# CT100-channel.net
KiCad netlist of a schematic drawn in Altium Designer
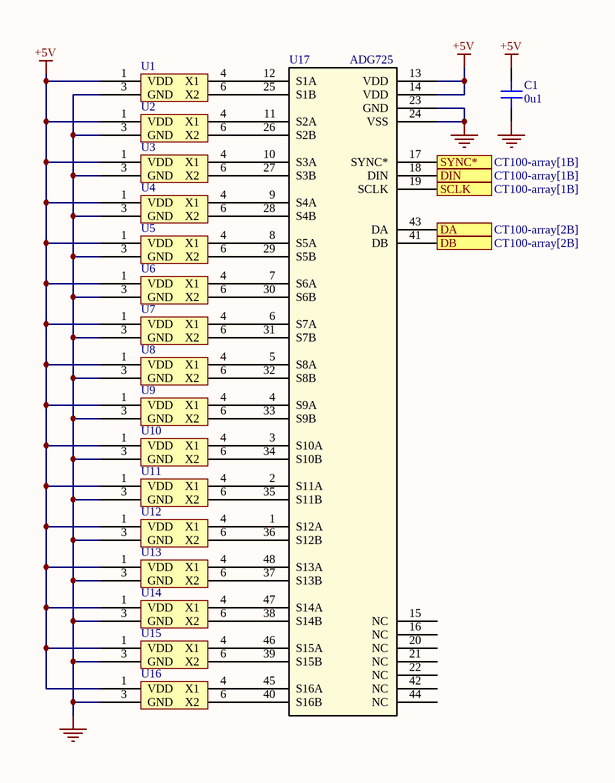
[diagram p0: CT100-channel.SchDoc]

(export (version "E")
  (design (tool "Eeschema 10.0.6"))
  (components
    (comp (ref "C1")
      (value "0u1")
      (footprint "CAP_0402")
      (description "Capacitor SMD 0402")
      (fields (field (name "VOLTAGE") "50V"))
      (libsource (lib "symbols") (part "CAP_0402"))
    )
    (comp (ref "U1")
      (value "CT100")
      (footprint "SON_6_CT100")
      (description "TMR Sensor, Linear, -40 to 85deg C")
      (fields
        (field (name "MANUFACTURER") "Crocus Technology")
        (field (name "MANUFACTURER PART NUMBER") "CT100LW-ID6")
      )
      (libsource (lib "symbols") (part "CT100LW-ID6-M"))
    )
    (comp (ref "U2")
      (value "CT100")
      (footprint "SON_6_CT100")
      (description "TMR Sensor, Linear, -40 to 85deg C")
      (fields
        (field (name "MANUFACTURER") "Crocus Technology")
        (field (name "MANUFACTURER PART NUMBER") "CT100LW-ID6")
      )
      (libsource (lib "symbols") (part "CT100LW-ID6-M"))
    )
    (comp (ref "U3")
      (value "CT100")
      (footprint "SON_6_CT100")
      (description "TMR Sensor, Linear, -40 to 85deg C")
      (fields
        (field (name "MANUFACTURER") "Crocus Technology")
        (field (name "MANUFACTURER PART NUMBER") "CT100LW-ID6")
      )
      (libsource (lib "symbols") (part "CT100LW-ID6-M"))
    )
    (comp (ref "U4")
      (value "CT100")
      (footprint "SON_6_CT100")
      (description "TMR Sensor, Linear, -40 to 85deg C")
      (fields
        (field (name "MANUFACTURER") "Crocus Technology")
        (field (name "MANUFACTURER PART NUMBER") "CT100LW-ID6")
      )
      (libsource (lib "symbols") (part "CT100LW-ID6-M"))
    )
    (comp (ref "U5")
      (value "CT100")
      (footprint "SON_6_CT100")
      (description "TMR Sensor, Linear, -40 to 85deg C")
      (fields
        (field (name "MANUFACTURER") "Crocus Technology")
        (field (name "MANUFACTURER PART NUMBER") "CT100LW-ID6")
      )
      (libsource (lib "symbols") (part "CT100LW-ID6-M"))
    )
    (comp (ref "U6")
      (value "CT100")
      (footprint "SON_6_CT100")
      (description "TMR Sensor, Linear, -40 to 85deg C")
      (fields
        (field (name "MANUFACTURER") "Crocus Technology")
        (field (name "MANUFACTURER PART NUMBER") "CT100LW-ID6")
      )
      (libsource (lib "symbols") (part "CT100LW-ID6-M"))
    )
    (comp (ref "U7")
      (value "CT100")
      (footprint "SON_6_CT100")
      (description "TMR Sensor, Linear, -40 to 85deg C")
      (fields
        (field (name "MANUFACTURER") "Crocus Technology")
        (field (name "MANUFACTURER PART NUMBER") "CT100LW-ID6")
      )
      (libsource (lib "symbols") (part "CT100LW-ID6-M"))
    )
    (comp (ref "U8")
      (value "CT100")
      (footprint "SON_6_CT100")
      (description "TMR Sensor, Linear, -40 to 85deg C")
      (fields
        (field (name "MANUFACTURER") "Crocus Technology")
        (field (name "MANUFACTURER PART NUMBER") "CT100LW-ID6")
      )
      (libsource (lib "symbols") (part "CT100LW-ID6-M"))
    )
    (comp (ref "U9")
      (value "CT100")
      (footprint "SON_6_CT100")
      (description "TMR Sensor, Linear, -40 to 85deg C")
      (fields
        (field (name "MANUFACTURER") "Crocus Technology")
        (field (name "MANUFACTURER PART NUMBER") "CT100LW-ID6")
      )
      (libsource (lib "symbols") (part "CT100LW-ID6-M"))
    )
    (comp (ref "U10")
      (value "CT100")
      (footprint "SON_6_CT100")
      (description "TMR Sensor, Linear, -40 to 85deg C")
      (fields
        (field (name "MANUFACTURER") "Crocus Technology")
        (field (name "MANUFACTURER PART NUMBER") "CT100LW-ID6")
      )
      (libsource (lib "symbols") (part "CT100LW-ID6-M"))
    )
    (comp (ref "U11")
      (value "CT100")
      (footprint "SON_6_CT100")
      (description "TMR Sensor, Linear, -40 to 85deg C")
      (fields
        (field (name "MANUFACTURER") "Crocus Technology")
        (field (name "MANUFACTURER PART NUMBER") "CT100LW-ID6")
      )
      (libsource (lib "symbols") (part "CT100LW-ID6-M"))
    )
    (comp (ref "U12")
      (value "CT100")
      (footprint "SON_6_CT100")
      (description "TMR Sensor, Linear, -40 to 85deg C")
      (fields
        (field (name "MANUFACTURER") "Crocus Technology")
        (field (name "MANUFACTURER PART NUMBER") "CT100LW-ID6")
      )
      (libsource (lib "symbols") (part "CT100LW-ID6-M"))
    )
    (comp (ref "U13")
      (value "CT100")
      (footprint "SON_6_CT100")
      (description "TMR Sensor, Linear, -40 to 85deg C")
      (fields
        (field (name "MANUFACTURER") "Crocus Technology")
        (field (name "MANUFACTURER PART NUMBER") "CT100LW-ID6")
      )
      (libsource (lib "symbols") (part "CT100LW-ID6-M"))
    )
    (comp (ref "U14")
      (value "CT100")
      (footprint "SON_6_CT100")
      (description "TMR Sensor, Linear, -40 to 85deg C")
      (fields
        (field (name "MANUFACTURER") "Crocus Technology")
        (field (name "MANUFACTURER PART NUMBER") "CT100LW-ID6")
      )
      (libsource (lib "symbols") (part "CT100LW-ID6-M"))
    )
    (comp (ref "U15")
      (value "CT100")
      (footprint "SON_6_CT100")
      (description "TMR Sensor, Linear, -40 to 85deg C")
      (fields
        (field (name "MANUFACTURER") "Crocus Technology")
        (field (name "MANUFACTURER PART NUMBER") "CT100LW-ID6")
      )
      (libsource (lib "symbols") (part "CT100LW-ID6-M"))
    )
    (comp (ref "U16")
      (value "CT100")
      (footprint "SON_6_CT100")
      (description "TMR Sensor, Linear, -40 to 85deg C")
      (fields
        (field (name "MANUFACTURER") "Crocus Technology")
        (field (name "MANUFACTURER PART NUMBER") "CT100LW-ID6")
      )
      (libsource (lib "symbols") (part "CT100LW-ID6-M"))
    )
    (comp (ref "U17")
      (value "ADG725")
      (footprint "SU_48_ADI")
      (description "Differential 16-Channel, Serially Controlled 3.5 Ω 1.8 V to 5.5 V, ±2.5 V, Analog Multiplexer")
      (fields (field (name "MANUFACTURER_PART_NUMBER") "ADG725BSUZ"))
      (libsource (lib "symbols") (part "ADG725BSUZ"))
    )
  )
  (nets
    (net (code "1") (name "+5V") (class "Default")
      (node (ref "C1") (pin "2") (pinfunction "2_2") (pintype "passive"))
      (node (ref "U1") (pin "1") (pinfunction "VDD_1") (pintype "power_in"))
      (node (ref "U10") (pin "1") (pinfunction "VDD_1") (pintype "power_in"))
      (node (ref "U11") (pin "1") (pinfunction "VDD_1") (pintype "power_in"))
      (node (ref "U12") (pin "1") (pinfunction "VDD_1") (pintype "power_in"))
      (node (ref "U13") (pin "1") (pinfunction "VDD_1") (pintype "power_in"))
      (node (ref "U14") (pin "1") (pinfunction "VDD_1") (pintype "power_in"))
      (node (ref "U15") (pin "1") (pinfunction "VDD_1") (pintype "power_in"))
      (node (ref "U16") (pin "1") (pinfunction "VDD_1") (pintype "power_in"))
      (node (ref "U17") (pin "13") (pinfunction "VDD_13") (pintype "power_in"))
      (node (ref "U17") (pin "14") (pinfunction "VDD_14") (pintype "power_in"))
      (node (ref "U2") (pin "1") (pinfunction "VDD_1") (pintype "power_in"))
      (node (ref "U3") (pin "1") (pinfunction "VDD_1") (pintype "power_in"))
      (node (ref "U4") (pin "1") (pinfunction "VDD_1") (pintype "power_in"))
      (node (ref "U5") (pin "1") (pinfunction "VDD_1") (pintype "power_in"))
      (node (ref "U6") (pin "1") (pinfunction "VDD_1") (pintype "power_in"))
      (node (ref "U7") (pin "1") (pinfunction "VDD_1") (pintype "power_in"))
      (node (ref "U8") (pin "1") (pinfunction "VDD_1") (pintype "power_in"))
      (node (ref "U9") (pin "1") (pinfunction "VDD_1") (pintype "power_in"))
    )
    (net (code "2") (name "/DA") (class "Default")
      (node (ref "U17") (pin "43") (pinfunction "DA_43") (pintype "passive"))
    )
    (net (code "3") (name "/DB") (class "Default")
      (node (ref "U17") (pin "41") (pinfunction "DB_41") (pintype "passive"))
    )
    (net (code "4") (name "/DIN") (class "Default")
      (node (ref "U17") (pin "18") (pinfunction "DIN_18") (pintype "passive"))
    )
    (net (code "5") (name "/SCLK") (class "Default")
      (node (ref "U17") (pin "19") (pinfunction "SCLK_19") (pintype "passive"))
    )
    (net (code "6") (name "/SYNC*") (class "Default")
      (node (ref "U17") (pin "17") (pinfunction "SYNC*_17") (pintype "passive"))
    )
    (net (code "7") (name "GND") (class "Default")
      (node (ref "C1") (pin "1") (pinfunction "1_1") (pintype "passive"))
      (node (ref "U1") (pin "3") (pinfunction "GND_3") (pintype "passive"))
      (node (ref "U10") (pin "3") (pinfunction "GND_3") (pintype "passive"))
      (node (ref "U11") (pin "3") (pinfunction "GND_3") (pintype "passive"))
      (node (ref "U12") (pin "3") (pinfunction "GND_3") (pintype "passive"))
      (node (ref "U13") (pin "3") (pinfunction "GND_3") (pintype "passive"))
      (node (ref "U14") (pin "3") (pinfunction "GND_3") (pintype "passive"))
      (node (ref "U15") (pin "3") (pinfunction "GND_3") (pintype "passive"))
      (node (ref "U16") (pin "3") (pinfunction "GND_3") (pintype "passive"))
      (node (ref "U17") (pin "23") (pinfunction "GND_23") (pintype "passive"))
      (node (ref "U17") (pin "24") (pinfunction "VSS_24") (pintype "power_in"))
      (node (ref "U2") (pin "3") (pinfunction "GND_3") (pintype "passive"))
      (node (ref "U3") (pin "3") (pinfunction "GND_3") (pintype "passive"))
      (node (ref "U4") (pin "3") (pinfunction "GND_3") (pintype "passive"))
      (node (ref "U5") (pin "3") (pinfunction "GND_3") (pintype "passive"))
      (node (ref "U6") (pin "3") (pinfunction "GND_3") (pintype "passive"))
      (node (ref "U7") (pin "3") (pinfunction "GND_3") (pintype "passive"))
      (node (ref "U8") (pin "3") (pinfunction "GND_3") (pintype "passive"))
      (node (ref "U9") (pin "3") (pinfunction "GND_3") (pintype "passive"))
    )
    (net (code "8") (name "Net-(U1-X1)") (class "Default")
      (node (ref "U1") (pin "4") (pinfunction "X1_4") (pintype "passive"))
      (node (ref "U17") (pin "12") (pinfunction "S1A_12") (pintype "passive"))
    )
    (net (code "9") (name "Net-(U1-X2)") (class "Default")
      (node (ref "U1") (pin "6") (pinfunction "X2_6") (pintype "passive"))
      (node (ref "U17") (pin "25") (pinfunction "S1B_25") (pintype "passive"))
    )
    (net (code "10") (name "Net-(U10-X1)") (class "Default")
      (node (ref "U10") (pin "4") (pinfunction "X1_4") (pintype "passive"))
      (node (ref "U17") (pin "3") (pinfunction "S10A_3") (pintype "passive"))
    )
    (net (code "11") (name "Net-(U10-X2)") (class "Default")
      (node (ref "U10") (pin "6") (pinfunction "X2_6") (pintype "passive"))
      (node (ref "U17") (pin "34") (pinfunction "S10B_34") (pintype "passive"))
    )
    (net (code "12") (name "Net-(U11-X1)") (class "Default")
      (node (ref "U11") (pin "4") (pinfunction "X1_4") (pintype "passive"))
      (node (ref "U17") (pin "2") (pinfunction "S11A_2") (pintype "passive"))
    )
    (net (code "13") (name "Net-(U11-X2)") (class "Default")
      (node (ref "U11") (pin "6") (pinfunction "X2_6") (pintype "passive"))
      (node (ref "U17") (pin "35") (pinfunction "S11B_35") (pintype "passive"))
    )
    (net (code "14") (name "Net-(U12-X1)") (class "Default")
      (node (ref "U12") (pin "4") (pinfunction "X1_4") (pintype "passive"))
      (node (ref "U17") (pin "1") (pinfunction "S12A_1") (pintype "passive"))
    )
    (net (code "15") (name "Net-(U12-X2)") (class "Default")
      (node (ref "U12") (pin "6") (pinfunction "X2_6") (pintype "passive"))
      (node (ref "U17") (pin "36") (pinfunction "S12B_36") (pintype "passive"))
    )
    (net (code "16") (name "Net-(U13-X1)") (class "Default")
      (node (ref "U13") (pin "4") (pinfunction "X1_4") (pintype "passive"))
      (node (ref "U17") (pin "48") (pinfunction "S13A_48") (pintype "passive"))
    )
    (net (code "17") (name "Net-(U13-X2)") (class "Default")
      (node (ref "U13") (pin "6") (pinfunction "X2_6") (pintype "passive"))
      (node (ref "U17") (pin "37") (pinfunction "S13B_37") (pintype "passive"))
    )
    (net (code "18") (name "Net-(U14-X1)") (class "Default")
      (node (ref "U14") (pin "4") (pinfunction "X1_4") (pintype "passive"))
      (node (ref "U17") (pin "47") (pinfunction "S14A_47") (pintype "passive"))
    )
    (net (code "19") (name "Net-(U14-X2)") (class "Default")
      (node (ref "U14") (pin "6") (pinfunction "X2_6") (pintype "passive"))
      (node (ref "U17") (pin "38") (pinfunction "S14B_38") (pintype "passive"))
    )
    (net (code "20") (name "Net-(U15-X1)") (class "Default")
      (node (ref "U15") (pin "4") (pinfunction "X1_4") (pintype "passive"))
      (node (ref "U17") (pin "46") (pinfunction "S15A_46") (pintype "passive"))
    )
    (net (code "21") (name "Net-(U15-X2)") (class "Default")
      (node (ref "U15") (pin "6") (pinfunction "X2_6") (pintype "passive"))
      (node (ref "U17") (pin "39") (pinfunction "S15B_39") (pintype "passive"))
    )
    (net (code "22") (name "Net-(U16-X1)") (class "Default")
      (node (ref "U16") (pin "4") (pinfunction "X1_4") (pintype "passive"))
      (node (ref "U17") (pin "45") (pinfunction "S16A_45") (pintype "passive"))
    )
    (net (code "23") (name "Net-(U16-X2)") (class "Default")
      (node (ref "U16") (pin "6") (pinfunction "X2_6") (pintype "passive"))
      (node (ref "U17") (pin "40") (pinfunction "S16B_40") (pintype "passive"))
    )
    (net (code "24") (name "Net-(U17-S2A)") (class "Default")
      (node (ref "U17") (pin "11") (pinfunction "S2A_11") (pintype "passive"))
      (node (ref "U2") (pin "4") (pinfunction "X1_4") (pintype "passive"))
    )
    (net (code "25") (name "Net-(U17-S2B)") (class "Default")
      (node (ref "U17") (pin "26") (pinfunction "S2B_26") (pintype "passive"))
      (node (ref "U2") (pin "6") (pinfunction "X2_6") (pintype "passive"))
    )
    (net (code "26") (name "Net-(U17-S3A)") (class "Default")
      (node (ref "U17") (pin "10") (pinfunction "S3A_10") (pintype "passive"))
      (node (ref "U3") (pin "4") (pinfunction "X1_4") (pintype "passive"))
    )
    (net (code "27") (name "Net-(U17-S3B)") (class "Default")
      (node (ref "U17") (pin "27") (pinfunction "S3B_27") (pintype "passive"))
      (node (ref "U3") (pin "6") (pinfunction "X2_6") (pintype "passive"))
    )
    (net (code "28") (name "Net-(U17-S4A)") (class "Default")
      (node (ref "U17") (pin "9") (pinfunction "S4A_9") (pintype "passive"))
      (node (ref "U4") (pin "4") (pinfunction "X1_4") (pintype "passive"))
    )
    (net (code "29") (name "Net-(U17-S4B)") (class "Default")
      (node (ref "U17") (pin "28") (pinfunction "S4B_28") (pintype "passive"))
      (node (ref "U4") (pin "6") (pinfunction "X2_6") (pintype "passive"))
    )
    (net (code "30") (name "Net-(U17-S5A)") (class "Default")
      (node (ref "U17") (pin "8") (pinfunction "S5A_8") (pintype "passive"))
      (node (ref "U5") (pin "4") (pinfunction "X1_4") (pintype "passive"))
    )
    (net (code "31") (name "Net-(U17-S5B)") (class "Default")
      (node (ref "U17") (pin "29") (pinfunction "S5B_29") (pintype "passive"))
      (node (ref "U5") (pin "6") (pinfunction "X2_6") (pintype "passive"))
    )
    (net (code "32") (name "Net-(U17-S6A)") (class "Default")
      (node (ref "U17") (pin "7") (pinfunction "S6A_7") (pintype "passive"))
      (node (ref "U6") (pin "4") (pinfunction "X1_4") (pintype "passive"))
    )
    (net (code "33") (name "Net-(U17-S6B)") (class "Default")
      (node (ref "U17") (pin "30") (pinfunction "S6B_30") (pintype "passive"))
      (node (ref "U6") (pin "6") (pinfunction "X2_6") (pintype "passive"))
    )
    (net (code "34") (name "Net-(U17-S7A)") (class "Default")
      (node (ref "U17") (pin "6") (pinfunction "S7A_6") (pintype "passive"))
      (node (ref "U7") (pin "4") (pinfunction "X1_4") (pintype "passive"))
    )
    (net (code "35") (name "Net-(U17-S7B)") (class "Default")
      (node (ref "U17") (pin "31") (pinfunction "S7B_31") (pintype "passive"))
      (node (ref "U7") (pin "6") (pinfunction "X2_6") (pintype "passive"))
    )
    (net (code "36") (name "Net-(U17-S8A)") (class "Default")
      (node (ref "U17") (pin "5") (pinfunction "S8A_5") (pintype "passive"))
      (node (ref "U8") (pin "4") (pinfunction "X1_4") (pintype "passive"))
    )
    (net (code "37") (name "Net-(U17-S8B)") (class "Default")
      (node (ref "U17") (pin "32") (pinfunction "S8B_32") (pintype "passive"))
      (node (ref "U8") (pin "6") (pinfunction "X2_6") (pintype "passive"))
    )
    (net (code "38") (name "Net-(U17-S9A)") (class "Default")
      (node (ref "U17") (pin "4") (pinfunction "S9A_4") (pintype "passive"))
      (node (ref "U9") (pin "4") (pinfunction "X1_4") (pintype "passive"))
    )
    (net (code "39") (name "Net-(U17-S9B)") (class "Default")
      (node (ref "U17") (pin "33") (pinfunction "S9B_33") (pintype "passive"))
      (node (ref "U9") (pin "6") (pinfunction "X2_6") (pintype "passive"))
    )
    (net (code "40") (name "unconnected-(U17-NC-Pad15)") (class "Default")
      (node (ref "U17") (pin "15") (pinfunction "NC_15") (pintype "passive"))
    )
    (net (code "41") (name "unconnected-(U17-NC-Pad16)") (class "Default")
      (node (ref "U17") (pin "16") (pinfunction "NC_16") (pintype "passive"))
    )
    (net (code "42") (name "unconnected-(U17-NC-Pad20)") (class "Default")
      (node (ref "U17") (pin "20") (pinfunction "NC_20") (pintype "passive"))
    )
    (net (code "43") (name "unconnected-(U17-NC-Pad21)") (class "Default")
      (node (ref "U17") (pin "21") (pinfunction "NC_21") (pintype "passive"))
    )
    (net (code "44") (name "unconnected-(U17-NC-Pad22)") (class "Default")
      (node (ref "U17") (pin "22") (pinfunction "NC_22") (pintype "passive"))
    )
    (net (code "45") (name "unconnected-(U17-NC-Pad42)") (class "Default")
      (node (ref "U17") (pin "42") (pinfunction "NC_42") (pintype "passive"))
    )
    (net (code "46") (name "unconnected-(U17-NC-Pad44)") (class "Default")
      (node (ref "U17") (pin "44") (pinfunction "NC_44") (pintype "passive"))
    )
  )
)
